# greenhousectrl-latest-compressed.net
KiCad netlist of a schematic drawn in EAGLE
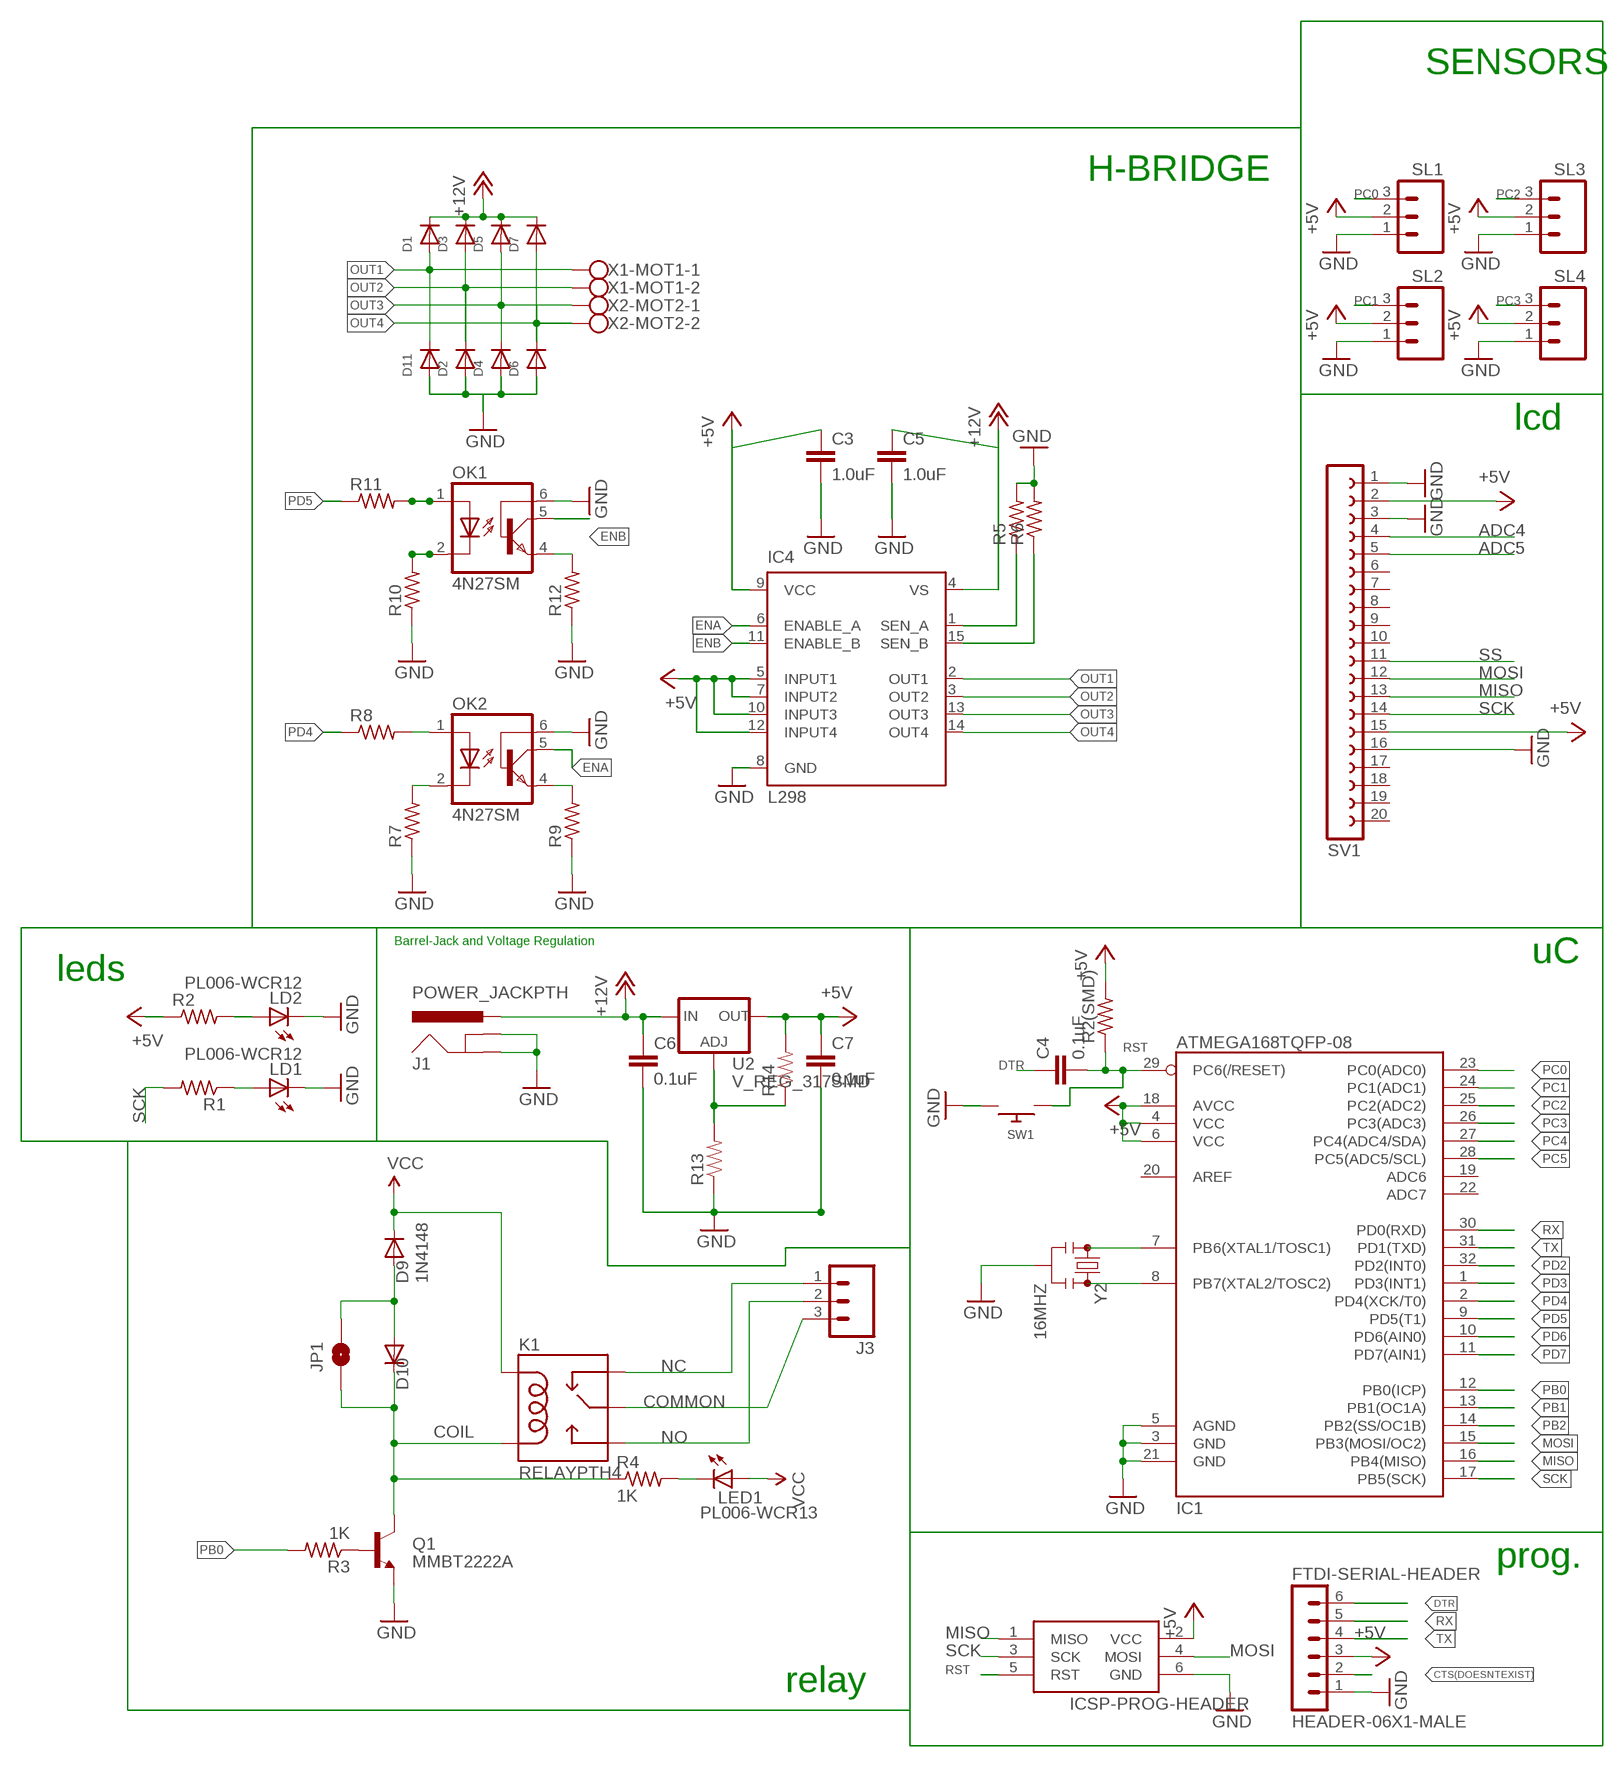
[diagram p0: schematic, sheet 1]

(export (version "E")
  (design (tool "Eeschema 10.0.6"))
  (components
    (comp (ref "C3")
      (value "1.0uF")
      (footprint "eagle-import:0805-CAP")
      (libsource (lib "eagle-import") (part "1.0UF-25V-+80/-20(0805){dblquote}"))
    )
    (comp (ref "C4")
      (value "0.1uF")
      (footprint "eagle-import:0603-CAP")
      (libsource (lib "eagle-import") (part "0.1UF-25V(+80/-20%)(0603)"))
    )
    (comp (ref "C5")
      (value "1.0uF")
      (footprint "eagle-import:0805-CAP")
      (libsource (lib "eagle-import") (part "1.0UF-25V-+80/-20(0805){dblquote}"))
    )
    (comp (ref "C6")
      (value "0.1uF")
      (footprint "eagle-import:0603-CAP")
      (libsource (lib "eagle-import") (part "0.1UF-25V(+80/-20%)(0603)"))
    )
    (comp (ref "C7")
      (value "0.1uF")
      (footprint "eagle-import:0603-CAP")
      (libsource (lib "eagle-import") (part "0.1UF-25V(+80/-20%)(0603)"))
    )
    (comp (ref "D1")
      (value "DIODESOD-523")
      (footprint "eagle-import:SOD-523")
      (libsource (lib "eagle-import") (part "DIODESOD-523"))
    )
    (comp (ref "D2")
      (value "DIODESOD-523")
      (footprint "eagle-import:SOD-523")
      (libsource (lib "eagle-import") (part "DIODESOD-523"))
    )
    (comp (ref "D3")
      (value "DIODESOD-523")
      (footprint "eagle-import:SOD-523")
      (libsource (lib "eagle-import") (part "DIODESOD-523"))
    )
    (comp (ref "D4")
      (value "DIODESOD-523")
      (footprint "eagle-import:SOD-523")
      (libsource (lib "eagle-import") (part "DIODESOD-523"))
    )
    (comp (ref "D5")
      (value "DIODESOD-523")
      (footprint "eagle-import:SOD-523")
      (libsource (lib "eagle-import") (part "DIODESOD-523"))
    )
    (comp (ref "D6")
      (value "DIODESOD-523")
      (footprint "eagle-import:SOD-523")
      (libsource (lib "eagle-import") (part "DIODESOD-523"))
    )
    (comp (ref "D7")
      (value "DIODESOD-523")
      (footprint "eagle-import:SOD-523")
      (libsource (lib "eagle-import") (part "DIODESOD-523"))
    )
    (comp (ref "D9")
      (value "1N4148")
      (footprint "eagle-import:SOD-323F")
      (libsource (lib "eagle-import") (part "DIODESOD-323F"))
    )
    (comp (ref "D10")
      (value "Zener")
      (footprint "eagle-import:SOD-323F")
      (libsource (lib "eagle-import") (part "DIODESOD-323F"))
    )
    (comp (ref "D11")
      (value "DIODESOD-523")
      (footprint "eagle-import:SOD-523")
      (libsource (lib "eagle-import") (part "DIODESOD-523"))
    )
    (comp (ref "FTDI-SERIAL-HEADER")
      (value "HEADER-06X1-MALE")
      (footprint "eagle-import:06X1-PTH")
      (libsource (lib "eagle-import") (part "HEADER-06X1?-MALE"))
    )
    (comp (ref "IC1")
      (value "ATMEGA168TQFP-08")
      (footprint "eagle-import:TQFP32-08")
      (libsource (lib "eagle-import") (part "ATMEGA168TQFP-08"))
    )
    (comp (ref "IC4")
      (value "L298")
      (footprint "eagle-import:MULTIWATT-15")
      (fields (field (name "MPN") "L298N"))
      (libsource (lib "eagle-import") (part "L298"))
    )
    (comp (ref "ICSP-PROG-HEADER")
      (value "AVRISP-6")
      (footprint "eagle-import:AVRISP")
      (libsource (lib "eagle-import") (part "AVRISP-6"))
    )
    (comp (ref "J1")
      (value "POWER_JACKPTH")
      (footprint "eagle-import:POWER_JACK_PTH")
      (libsource (lib "eagle-import") (part "POWER_JACKPTH"))
    )
    (comp (ref "J3")
      (value "M03-SCREW-5MM")
      (footprint "eagle-import:SCREWTERMINAL-5MM-3")
      (libsource (lib "eagle-import") (part "M03-SCREW-5MM"))
    )
    (comp (ref "JP1")
      (value "JUMPER-PAD-2-NOYES_SILK")
      (footprint "eagle-import:PAD-JUMPER-2-NO_YES_SILK")
      (libsource (lib "eagle-import") (part "JUMPER-PAD-2-NOYES_SILK"))
    )
    (comp (ref "K1")
      (value "RELAYPTH4")
      (footprint "eagle-import:RELAY-JZC")
      (libsource (lib "eagle-import") (part "RELAYPTH4"))
    )
    (comp (ref "LD1")
      (value "PL006-WCR12")
      (footprint "eagle-import:SOT23")
      (libsource (lib "eagle-import") (part "PL006-WCR12"))
    )
    (comp (ref "LD2")
      (value "PL006-WCR12")
      (footprint "eagle-import:SOT23")
      (libsource (lib "eagle-import") (part "PL006-WCR12"))
    )
    (comp (ref "LED1")
      (value "PL006-WCR13")
      (footprint "eagle-import:SOT23")
      (fields (field (name "PROD_ID") "DIO-09529"))
      (libsource (lib "eagle-import") (part "PL006-WCR13"))
    )
    (comp (ref "OK1")
      (value "4N27SM")
      (footprint "eagle-import:DIL6-SMD")
      (fields (field (name "MF") "FAIRCHILD SEMICONDUCTOR") (field (name "MPN") "4N27S-M"))
      (libsource (lib "eagle-import") (part "4N?MS27"))
    )
    (comp (ref "OK2")
      (value "4N27SM")
      (footprint "eagle-import:DIL6-SMD")
      (fields (field (name "MF") "FAIRCHILD SEMICONDUCTOR") (field (name "MPN") "4N27S-M"))
      (libsource (lib "eagle-import") (part "4N?MS27"))
    )
    (comp (ref "Q1")
      (value "MMBT2222A")
      (footprint "eagle-import:SOT23-3")
      (libsource (lib "eagle-import") (part "TRANSISTOR_NPNMMBT2222A"))
    )
    (comp (ref "R1")
      (value "R-US_M0805")
      (footprint "eagle-import:M0805")
      (libsource (lib "eagle-import") (part "R-US_M0805"))
    )
    (comp (ref "R2")
      (value "R-US_M0805")
      (footprint "eagle-import:M0805")
      (libsource (lib "eagle-import") (part "R-US_M0805"))
    )
    (comp (ref "R2(SMD)")
      (value "R-US_M0805")
      (footprint "eagle-import:M0805")
      (libsource (lib "eagle-import") (part "R-US_M0805"))
    )
    (comp (ref "R3")
      (value "1K")
      (footprint "eagle-import:M0805")
      (libsource (lib "eagle-import") (part "R-US_M0805"))
    )
    (comp (ref "R4")
      (value "1K")
      (footprint "eagle-import:M0805")
      (libsource (lib "eagle-import") (part "R-US_M0805"))
    )
    (comp (ref "R5")
      (value "R-US_M0805")
      (footprint "eagle-import:M0805")
      (libsource (lib "eagle-import") (part "R-US_M0805"))
    )
    (comp (ref "R6")
      (value "R-US_M0805")
      (footprint "eagle-import:M0805")
      (libsource (lib "eagle-import") (part "R-US_M0805"))
    )
    (comp (ref "R7")
      (value "R-US_M0805")
      (footprint "eagle-import:M0805")
      (libsource (lib "eagle-import") (part "R-US_M0805"))
    )
    (comp (ref "R8")
      (value "R-US_M0805")
      (footprint "eagle-import:M0805")
      (libsource (lib "eagle-import") (part "R-US_M0805"))
    )
    (comp (ref "R9")
      (value "R-US_M0805")
      (footprint "eagle-import:M0805")
      (libsource (lib "eagle-import") (part "R-US_M0805"))
    )
    (comp (ref "R10")
      (value "R-US_M0805")
      (footprint "eagle-import:M0805")
      (libsource (lib "eagle-import") (part "R-US_M0805"))
    )
    (comp (ref "R11")
      (value "R-US_M0805")
      (footprint "eagle-import:M0805")
      (libsource (lib "eagle-import") (part "R-US_M0805"))
    )
    (comp (ref "R12")
      (value "R-US_M0805")
      (footprint "eagle-import:M0805")
      (libsource (lib "eagle-import") (part "R-US_M0805"))
    )
    (comp (ref "R13")
      (value "RESISTOR0402")
      (footprint "eagle-import:0402-RES")
      (libsource (lib "eagle-import") (part "RESISTOR0402"))
    )
    (comp (ref "R14")
      (value "RESISTOR0402")
      (footprint "eagle-import:0402-RES")
      (libsource (lib "eagle-import") (part "RESISTOR0402"))
    )
    (comp (ref "SL1")
      (value "M03")
      (footprint "eagle-import:03P")
      (libsource (lib "eagle-import") (part "M03"))
    )
    (comp (ref "SL2")
      (value "M03")
      (footprint "eagle-import:03P")
      (libsource (lib "eagle-import") (part "M03"))
    )
    (comp (ref "SL3")
      (value "M03")
      (footprint "eagle-import:03P")
      (libsource (lib "eagle-import") (part "M03"))
    )
    (comp (ref "SL4")
      (value "M03")
      (footprint "eagle-import:03P")
      (libsource (lib "eagle-import") (part "M03"))
    )
    (comp (ref "SV1")
      (value "FE20-1")
      (footprint "eagle-import:FE20")
      (libsource (lib "eagle-import") (part "FE20-1"))
    )
    (comp (ref "SW1")
      (value "SWITCH_PUSHBUTTONC&K_KSS")
      (footprint "eagle-import:BTN_CK_KSS")
      (libsource (lib "eagle-import") (part "SWITCH_PUSHBUTTONC&K_KSS"))
    )
    (comp (ref "U2")
      (value "V_REG_317SMD")
      (footprint "eagle-import:SOT223")
      (libsource (lib "eagle-import") (part "V_REG_317SMD"))
    )
    (comp (ref "X1-MOT1")
      (value "W237-102")
      (footprint "eagle-import:W237-102")
      (fields (field (name "MPN") "237-102"))
      (libsource (lib "eagle-import") (part "W237-102"))
    )
    (comp (ref "X2-MOT2")
      (value "W237-102")
      (footprint "eagle-import:W237-102")
      (fields (field (name "MPN") "237-102"))
      (libsource (lib "eagle-import") (part "W237-102"))
    )
    (comp (ref "Y2")
      (value "16MHZ")
      (footprint "eagle-import:RESONATOR-SMD")
      (libsource (lib "eagle-import") (part "RESONATOR16MHZ"))
    )
  )
  (nets
    (net (code "1") (name "+5V") (class "Default")
      (node (ref "C3") (pin "1") (pinfunction "1_1") (pintype "passive"))
      (node (ref "C7") (pin "1") (pinfunction "1_1") (pintype "passive"))
      (node (ref "FTDI-SERIAL-HEADER") (pin "3") (pinfunction "3_3") (pintype "passive"))
      (node (ref "IC1") (pin "18") (pinfunction "AVCC_18") (pintype "bidirectional"))
      (node (ref "IC1") (pin "4") (pinfunction "VCC_4") (pintype "bidirectional"))
      (node (ref "IC1") (pin "6") (pinfunction "VCC_6") (pintype "bidirectional"))
      (node (ref "IC4") (pin "10") (pinfunction "INPUT3_10") (pintype "input"))
      (node (ref "IC4") (pin "12") (pinfunction "INPUT4_12") (pintype "input"))
      (node (ref "IC4") (pin "5") (pinfunction "INPUT1_5") (pintype "input"))
      (node (ref "IC4") (pin "7") (pinfunction "INPUT2_7") (pintype "input"))
      (node (ref "IC4") (pin "9") (pinfunction "VCC_9") (pintype "power_in"))
      (node (ref "ICSP-PROG-HEADER") (pin "2") (pinfunction "VCC_2") (pintype "power_in"))
      (node (ref "R14") (pin "2") (pinfunction "2_2") (pintype "passive"))
      (node (ref "R2") (pin "1") (pinfunction "1_1") (pintype "passive"))
      (node (ref "R2(SMD)") (pin "2") (pinfunction "2_2") (pintype "passive"))
      (node (ref "SL1") (pin "2") (pinfunction "2_2") (pintype "passive"))
      (node (ref "SL2") (pin "2") (pinfunction "2_2") (pintype "passive"))
      (node (ref "SL3") (pin "2") (pinfunction "2_2") (pintype "passive"))
      (node (ref "SL4") (pin "2") (pinfunction "2_2") (pintype "passive"))
      (node (ref "SV1") (pin "15") (pinfunction "15_15") (pintype "passive"))
      (node (ref "SV1") (pin "2") (pinfunction "2_2") (pintype "passive"))
      (node (ref "U2") (pin "2") (pinfunction "OUT_2") (pintype "output"))
    )
    (net (code "2") (name "+12V") (class "Default")
      (node (ref "C5") (pin "1") (pinfunction "1_1") (pintype "passive"))
      (node (ref "C6") (pin "1") (pinfunction "1_1") (pintype "passive"))
      (node (ref "D1") (pin "K") (pinfunction "C_K") (pintype "passive"))
      (node (ref "D3") (pin "K") (pinfunction "C_K") (pintype "passive"))
      (node (ref "D5") (pin "K") (pinfunction "C_K") (pintype "passive"))
      (node (ref "D7") (pin "K") (pinfunction "C_K") (pintype "passive"))
      (node (ref "IC4") (pin "4") (pinfunction "VS_4") (pintype "power_in"))
      (node (ref "J1") (pin "PWR") (pinfunction "PWR_PWR") (pintype "bidirectional"))
      (node (ref "U2") (pin "3") (pinfunction "IN_3") (pintype "input"))
    )
    (net (code "3") (name "/ADC4") (class "Default")
      (node (ref "SV1") (pin "4") (pinfunction "4_4") (pintype "passive"))
    )
    (net (code "4") (name "/ADC5") (class "Default")
      (node (ref "SV1") (pin "5") (pinfunction "5_5") (pintype "passive"))
    )
    (net (code "5") (name "/COIL") (class "Default")
      (node (ref "D10") (pin "C") (pinfunction "C_C") (pintype "passive"))
      (node (ref "JP1") (pin "1") (pinfunction "1_1") (pintype "passive"))
      (node (ref "K1") (pin "1") (pinfunction "COIL2_1") (pintype "bidirectional"))
      (node (ref "Q1") (pin "3") (pinfunction "C_3") (pintype "passive"))
      (node (ref "R4") (pin "1") (pinfunction "1_1") (pintype "passive"))
    )
    (net (code "6") (name "/COMMON") (class "Default")
      (node (ref "J3") (pin "3") (pinfunction "3_3") (pintype "passive"))
      (node (ref "K1") (pin "4") (pinfunction "MAIN_4") (pintype "bidirectional"))
    )
    (net (code "7") (name "/NC") (class "Default")
      (node (ref "J3") (pin "1") (pinfunction "1_1") (pintype "passive"))
      (node (ref "K1") (pin "2") (pinfunction "NC_2") (pintype "bidirectional"))
    )
    (net (code "8") (name "/NO") (class "Default")
      (node (ref "J3") (pin "2") (pinfunction "2_2") (pintype "passive"))
      (node (ref "K1") (pin "3") (pinfunction "NO_3") (pintype "bidirectional"))
    )
    (net (code "9") (name "/RST") (class "Default")
      (node (ref "C4") (pin "2") (pinfunction "2_2") (pintype "passive"))
      (node (ref "IC1") (pin "29") (pinfunction "PC6(/RESET)_29") (pintype "bidirectional"))
      (node (ref "ICSP-PROG-HEADER") (pin "5") (pinfunction "RST_5") (pintype "output"))
      (node (ref "R2(SMD)") (pin "1") (pinfunction "1_1") (pintype "passive"))
      (node (ref "SW1") (pin "P$1") (pinfunction "P$1_P$1") (pintype "passive"))
    )
    (net (code "10") (name "/SS") (class "Default")
      (node (ref "SV1") (pin "11") (pinfunction "11_11") (pintype "passive"))
    )
    (net (code "11") (name "CTS(DOESNTEXIST)") (class "Default")
      (node (ref "FTDI-SERIAL-HEADER") (pin "2") (pinfunction "2_2") (pintype "passive"))
    )
    (net (code "12") (name "DTR") (class "Default")
      (node (ref "C4") (pin "1") (pinfunction "1_1") (pintype "passive"))
      (node (ref "FTDI-SERIAL-HEADER") (pin "6") (pinfunction "6_6") (pintype "passive"))
    )
    (net (code "13") (name "ENA") (class "Default")
      (node (ref "IC4") (pin "6") (pinfunction "ENABLE_A_6") (pintype "input"))
      (node (ref "OK2") (pin "5") (pinfunction "COL_5") (pintype "passive"))
    )
    (net (code "14") (name "ENB") (class "Default")
      (node (ref "IC4") (pin "11") (pinfunction "ENABLE_B_11") (pintype "input"))
      (node (ref "OK1") (pin "5") (pinfunction "COL_5") (pintype "passive"))
    )
    (net (code "15") (name "GND") (class "Default")
      (node (ref "C3") (pin "2") (pinfunction "2_2") (pintype "passive"))
      (node (ref "C5") (pin "2") (pinfunction "2_2") (pintype "passive"))
      (node (ref "C6") (pin "2") (pinfunction "2_2") (pintype "passive"))
      (node (ref "C7") (pin "2") (pinfunction "2_2") (pintype "passive"))
      (node (ref "D11") (pin "A") (pinfunction "A_A") (pintype "passive"))
      (node (ref "D2") (pin "A") (pinfunction "A_A") (pintype "passive"))
      (node (ref "D4") (pin "A") (pinfunction "A_A") (pintype "passive"))
      (node (ref "D6") (pin "A") (pinfunction "A_A") (pintype "passive"))
      (node (ref "FTDI-SERIAL-HEADER") (pin "1") (pinfunction "1_1") (pintype "passive"))
      (node (ref "IC1") (pin "21") (pinfunction "GND_21") (pintype "bidirectional"))
      (node (ref "IC1") (pin "3") (pinfunction "GND_3") (pintype "bidirectional"))
      (node (ref "IC1") (pin "5") (pinfunction "AGND_5") (pintype "bidirectional"))
      (node (ref "IC4") (pin "8") (pinfunction "GND_8") (pintype "power_in"))
      (node (ref "ICSP-PROG-HEADER") (pin "6") (pinfunction "GND_6") (pintype "power_in"))
      (node (ref "J1") (pin "GND") (pinfunction "GND_GND") (pintype "bidirectional"))
      (node (ref "J1") (pin "GNDBREAK") (pinfunction "GNDBREAK_GNDBREAK") (pintype "bidirectional"))
      (node (ref "LD1") (pin "3") (pinfunction "C_3") (pintype "passive"))
      (node (ref "LD2") (pin "3") (pinfunction "C_3") (pintype "passive"))
      (node (ref "OK1") (pin "6") (pinfunction "BAS_6") (pintype "passive"))
      (node (ref "OK2") (pin "6") (pinfunction "BAS_6") (pintype "passive"))
      (node (ref "Q1") (pin "2") (pinfunction "E_2") (pintype "passive"))
      (node (ref "R10") (pin "1") (pinfunction "1_1") (pintype "passive"))
      (node (ref "R12") (pin "1") (pinfunction "1_1") (pintype "passive"))
      (node (ref "R13") (pin "1") (pinfunction "1_1") (pintype "passive"))
      (node (ref "R5") (pin "2") (pinfunction "2_2") (pintype "passive"))
      (node (ref "R6") (pin "2") (pinfunction "2_2") (pintype "passive"))
      (node (ref "R7") (pin "1") (pinfunction "1_1") (pintype "passive"))
      (node (ref "R9") (pin "1") (pinfunction "1_1") (pintype "passive"))
      (node (ref "SL1") (pin "1") (pinfunction "1_1") (pintype "passive"))
      (node (ref "SL2") (pin "1") (pinfunction "1_1") (pintype "passive"))
      (node (ref "SL3") (pin "1") (pinfunction "1_1") (pintype "passive"))
      (node (ref "SL4") (pin "1") (pinfunction "1_1") (pintype "passive"))
      (node (ref "SV1") (pin "1") (pinfunction "1_1") (pintype "passive"))
      (node (ref "SV1") (pin "16") (pinfunction "16_16") (pintype "passive"))
      (node (ref "SV1") (pin "3") (pinfunction "3_3") (pintype "passive"))
      (node (ref "SW1") (pin "P$2") (pinfunction "P$2_P$2") (pintype "passive"))
      (node (ref "Y2") (pin "2") (pinfunction "2_2") (pintype "passive"))
    )
    (net (code "16") (name "MISO") (class "Default")
      (node (ref "IC1") (pin "16") (pinfunction "PB4(MISO)_16") (pintype "bidirectional"))
      (node (ref "ICSP-PROG-HEADER") (pin "1") (pinfunction "MISO_1") (pintype "input"))
      (node (ref "SV1") (pin "13") (pinfunction "13_13") (pintype "passive"))
    )
    (net (code "17") (name "MOSI") (class "Default")
      (node (ref "IC1") (pin "15") (pinfunction "PB3(MOSI/OC2)_15") (pintype "bidirectional"))
      (node (ref "ICSP-PROG-HEADER") (pin "4") (pinfunction "MOSI_4") (pintype "output"))
      (node (ref "SV1") (pin "12") (pinfunction "12_12") (pintype "passive"))
    )
    (net (code "18") (name "Net-(D10-PadA)") (class "Default")
      (node (ref "D10") (pin "A") (pinfunction "A_A") (pintype "passive"))
      (node (ref "D9") (pin "A") (pinfunction "A_A") (pintype "passive"))
      (node (ref "JP1") (pin "2") (pinfunction "2_2") (pintype "passive"))
    )
    (net (code "19") (name "Net-(IC1-PB6(XTAL1{slash}TOSC1))") (class "Default")
      (node (ref "IC1") (pin "7") (pinfunction "PB6(XTAL1/TOSC1)_7") (pintype "bidirectional"))
      (node (ref "Y2") (pin "1") (pinfunction "1_1") (pintype "passive"))
    )
    (net (code "20") (name "Net-(IC1-PB7(XTAL2{slash}TOSC2))") (class "Default")
      (node (ref "IC1") (pin "8") (pinfunction "PB7(XTAL2/TOSC2)_8") (pintype "bidirectional"))
      (node (ref "Y2") (pin "3") (pinfunction "3_3") (pintype "passive"))
    )
    (net (code "21") (name "Net-(IC4-SEN_A)") (class "Default")
      (node (ref "IC4") (pin "1") (pinfunction "SEN_A_1") (pintype "input"))
      (node (ref "R5") (pin "1") (pinfunction "1_1") (pintype "passive"))
    )
    (net (code "22") (name "Net-(IC4-SEN_B)") (class "Default")
      (node (ref "IC4") (pin "15") (pinfunction "SEN_B_15") (pintype "input"))
      (node (ref "R6") (pin "1") (pinfunction "1_1") (pintype "passive"))
    )
    (net (code "23") (name "Net-(LD1-A)") (class "Default")
      (node (ref "LD1") (pin "1") (pinfunction "A_1") (pintype "passive"))
      (node (ref "R1") (pin "1") (pinfunction "1_1") (pintype "passive"))
    )
    (net (code "24") (name "Net-(LD2-A)") (class "Default")
      (node (ref "LD2") (pin "1") (pinfunction "A_1") (pintype "passive"))
      (node (ref "R2") (pin "2") (pinfunction "2_2") (pintype "passive"))
    )
    (net (code "25") (name "Net-(LED1-C)") (class "Default")
      (node (ref "LED1") (pin "3") (pinfunction "C_3") (pintype "passive"))
      (node (ref "R4") (pin "2") (pinfunction "2_2") (pintype "passive"))
    )
    (net (code "26") (name "Net-(OK1-A)") (class "Default")
      (node (ref "OK1") (pin "1") (pinfunction "A_1") (pintype "passive"))
      (node (ref "R11") (pin "2") (pinfunction "2_2") (pintype "passive"))
    )
    (net (code "27") (name "Net-(OK1-C)") (class "Default")
      (node (ref "OK1") (pin "2") (pinfunction "C_2") (pintype "passive"))
      (node (ref "R10") (pin "2") (pinfunction "2_2") (pintype "passive"))
    )
    (net (code "28") (name "Net-(OK1-EMI)") (class "Default")
      (node (ref "OK1") (pin "4") (pinfunction "EMI_4") (pintype "passive"))
      (node (ref "R12") (pin "2") (pinfunction "2_2") (pintype "passive"))
    )
    (net (code "29") (name "Net-(OK2-A)") (class "Default")
      (node (ref "OK2") (pin "1") (pinfunction "A_1") (pintype "passive"))
      (node (ref "R8") (pin "2") (pinfunction "2_2") (pintype "passive"))
    )
    (net (code "30") (name "Net-(OK2-C)") (class "Default")
      (node (ref "OK2") (pin "2") (pinfunction "C_2") (pintype "passive"))
      (node (ref "R7") (pin "2") (pinfunction "2_2") (pintype "passive"))
    )
    (net (code "31") (name "Net-(OK2-EMI)") (class "Default")
      (node (ref "OK2") (pin "4") (pinfunction "EMI_4") (pintype "passive"))
      (node (ref "R9") (pin "2") (pinfunction "2_2") (pintype "passive"))
    )
    (net (code "32") (name "Net-(Q1-B)") (class "Default")
      (node (ref "Q1") (pin "1") (pinfunction "B_1") (pintype "passive"))
      (node (ref "R3") (pin "1") (pinfunction "1_1") (pintype "passive"))
    )
    (net (code "33") (name "Net-(U2-ADJ)") (class "Default")
      (node (ref "R13") (pin "2") (pinfunction "2_2") (pintype "passive"))
      (node (ref "R14") (pin "1") (pinfunction "1_1") (pintype "passive"))
      (node (ref "U2") (pin "1") (pinfunction "ADJ_1") (pintype "input"))
    )
    (net (code "34") (name "OUT1") (class "Default")
      (node (ref "D1") (pin "A") (pinfunction "A_A") (pintype "passive"))
      (node (ref "D11") (pin "K") (pinfunction "C_K") (pintype "passive"))
      (node (ref "IC4") (pin "2") (pinfunction "OUT1_2") (pintype "output"))
      (node (ref "X1-MOT1") (pin "1") (pinfunction "KL_1") (pintype "passive"))
    )
    (net (code "35") (name "OUT2") (class "Default")
      (node (ref "D2") (pin "K") (pinfunction "C_K") (pintype "passive"))
      (node (ref "D3") (pin "A") (pinfunction "A_A") (pintype "passive"))
      (node (ref "IC4") (pin "3") (pinfunction "OUT2_3") (pintype "output"))
      (node (ref "X1-MOT1") (pin "2") (pinfunction "KL_2") (pintype "passive"))
    )
    (net (code "36") (name "OUT3") (class "Default")
      (node (ref "D4") (pin "K") (pinfunction "C_K") (pintype "passive"))
      (node (ref "D5") (pin "A") (pinfunction "A_A") (pintype "passive"))
      (node (ref "IC4") (pin "13") (pinfunction "OUT3_13") (pintype "output"))
      (node (ref "X2-MOT2") (pin "1") (pinfunction "KL_1") (pintype "passive"))
    )
    (net (code "37") (name "OUT4") (class "Default")
      (node (ref "D6") (pin "K") (pinfunction "C_K") (pintype "passive"))
      (node (ref "D7") (pin "A") (pinfunction "A_A") (pintype "passive"))
      (node (ref "IC4") (pin "14") (pinfunction "OUT4_14") (pintype "output"))
      (node (ref "X2-MOT2") (pin "2") (pinfunction "KL_2") (pintype "passive"))
    )
    (net (code "38") (name "PB0") (class "Default")
      (node (ref "IC1") (pin "12") (pinfunction "PB0(ICP)_12") (pintype "bidirectional"))
      (node (ref "R3") (pin "2") (pinfunction "2_2") (pintype "passive"))
    )
    (net (code "39") (name "PB1") (class "Default")
      (node (ref "IC1") (pin "13") (pinfunction "PB1(OC1A)_13") (pintype "bidirectional"))
    )
    (net (code "40") (name "PB2") (class "Default")
      (node (ref "IC1") (pin "14") (pinfunction "PB2(SS/OC1B)_14") (pintype "bidirectional"))
    )
    (net (code "41") (name "PC0") (class "Default")
      (node (ref "IC1") (pin "23") (pinfunction "PC0(ADC0)_23") (pintype "bidirectional"))
      (node (ref "SL1") (pin "3") (pinfunction "3_3") (pintype "passive"))
    )
    (net (code "42") (name "PC1") (class "Default")
      (node (ref "IC1") (pin "24") (pinfunction "PC1(ADC1)_24") (pintype "bidirectional"))
      (node (ref "SL2") (pin "3") (pinfunction "3_3") (pintype "passive"))
    )
    (net (code "43") (name "PC2") (class "Default")
      (node (ref "IC1") (pin "25") (pinfunction "PC2(ADC2)_25") (pintype "bidirectional"))
      (node (ref "SL3") (pin "3") (pinfunction "3_3") (pintype "passive"))
    )
    (net (code "44") (name "PC3") (class "Default")
      (node (ref "IC1") (pin "26") (pinfunction "PC3(ADC3)_26") (pintype "bidirectional"))
      (node (ref "SL4") (pin "3") (pinfunction "3_3") (pintype "passive"))
    )
    (net (code "45") (name "PC4") (class "Default")
      (node (ref "IC1") (pin "27") (pinfunction "PC4(ADC4/SDA)_27") (pintype "bidirectional"))
    )
    (net (code "46") (name "PC5") (class "Default")
      (node (ref "IC1") (pin "28") (pinfunction "PC5(ADC5/SCL)_28") (pintype "bidirectional"))
    )
    (net (code "47") (name "PD2") (class "Default")
      (node (ref "IC1") (pin "32") (pinfunction "PD2(INT0)_32") (pintype "bidirectional"))
    )
    (net (code "48") (name "PD3") (class "Default")
      (node (ref "IC1") (pin "1") (pinfunction "PD3(INT1)_1") (pintype "bidirectional"))
    )
    (net (code "49") (name "PD4") (class "Default")
      (node (ref "IC1") (pin "2") (pinfunction "PD4(XCK/T0)_2") (pintype "bidirectional"))
      (node (ref "R8") (pin "1") (pinfunction "1_1") (pintype "passive"))
    )
    (net (code "50") (name "PD5") (class "Default")
      (node (ref "IC1") (pin "9") (pinfunction "PD5(T1)_9") (pintype "bidirectional"))
      (node (ref "R11") (pin "1") (pinfunction "1_1") (pintype "passive"))
    )
    (net (code "51") (name "PD6") (class "Default")
      (node (ref "IC1") (pin "10") (pinfunction "PD6(AIN0)_10") (pintype "bidirectional"))
    )
    (net (code "52") (name "PD7") (class "Default")
      (node (ref "IC1") (pin "11") (pinfunction "PD7(AIN1)_11") (pintype "bidirectional"))
    )
    (net (code "53") (name "RX") (class "Default")
      (node (ref "FTDI-SERIAL-HEADER") (pin "5") (pinfunction "5_5") (pintype "passive"))
      (node (ref "IC1") (pin "30") (pinfunction "PD0(RXD)_30") (pintype "bidirectional"))
    )
    (net (code "54") (name "SCK") (class "Default")
      (node (ref "IC1") (pin "17") (pinfunction "PB5(SCK)_17") (pintype "bidirectional"))
      (node (ref "ICSP-PROG-HEADER") (pin "3") (pinfunction "SCK_3") (pintype "output"))
      (node (ref "R1") (pin "2") (pinfunction "2_2") (pintype "passive"))
      (node (ref "SV1") (pin "14") (pinfunction "14_14") (pintype "passive"))
    )
    (net (code "55") (name "TX") (class "Default")
      (node (ref "FTDI-SERIAL-HEADER") (pin "4") (pinfunction "4_4") (pintype "passive"))
      (node (ref "IC1") (pin "31") (pinfunction "PD1(TXD)_31") (pintype "bidirectional"))
    )
    (net (code "56") (name "VCC") (class "Default")
      (node (ref "D9") (pin "C") (pinfunction "C_C") (pintype "passive"))
      (node (ref "K1") (pin "5") (pinfunction "COIL1_5") (pintype "bidirectional"))
      (node (ref "LED1") (pin "1") (pinfunction "A_1") (pintype "passive"))
    )
    (net (code "57") (name "unconnected-(IC1-ADC6-Pad19)") (class "Default")
      (node (ref "IC1") (pin "19") (pinfunction "ADC6_19") (pintype "bidirectional"))
    )
    (net (code "58") (name "unconnected-(IC1-ADC7-Pad22)") (class "Default")
      (node (ref "IC1") (pin "22") (pinfunction "ADC7_22") (pintype "bidirectional"))
    )
    (net (code "59") (name "unconnected-(IC1-AREF-Pad20)") (class "Default")
      (node (ref "IC1") (pin "20") (pinfunction "AREF_20") (pintype "bidirectional"))
    )
    (net (code "60") (name "unconnected-(SV1-Pad6)") (class "Default")
      (node (ref "SV1") (pin "6") (pinfunction "6_6") (pintype "passive"))
    )
    (net (code "61") (name "unconnected-(SV1-Pad7)") (class "Default")
      (node (ref "SV1") (pin "7") (pinfunction "7_7") (pintype "passive"))
    )
    (net (code "62") (name "unconnected-(SV1-Pad8)") (class "Default")
      (node (ref "SV1") (pin "8") (pinfunction "8_8") (pintype "passive"))
    )
    (net (code "63") (name "unconnected-(SV1-Pad9)") (class "Default")
      (node (ref "SV1") (pin "9") (pinfunction "9_9") (pintype "passive"))
    )
    (net (code "64") (name "unconnected-(SV1-Pad10)") (class "Default")
      (node (ref "SV1") (pin "10") (pinfunction "10_10") (pintype "passive"))
    )
    (net (code "65") (name "unconnected-(SV1-Pad17)") (class "Default")
      (node (ref "SV1") (pin "17") (pinfunction "17_17") (pintype "passive"))
    )
    (net (code "66") (name "unconnected-(SV1-Pad18)") (class "Default")
      (node (ref "SV1") (pin "18") (pinfunction "18_18") (pintype "passive"))
    )
    (net (code "67") (name "unconnected-(SV1-Pad19)") (class "Default")
      (node (ref "SV1") (pin "19") (pinfunction "19_19") (pintype "passive"))
    )
    (net (code "68") (name "unconnected-(SV1-Pad20)") (class "Default")
      (node (ref "SV1") (pin "20") (pinfunction "20_20") (pintype "passive"))
    )
  )
)
